# 2026-01-18_TinZr_Rev5_EasyEDA_project.net
KiCad netlist of a schematic drawn in EasyEDA Pro
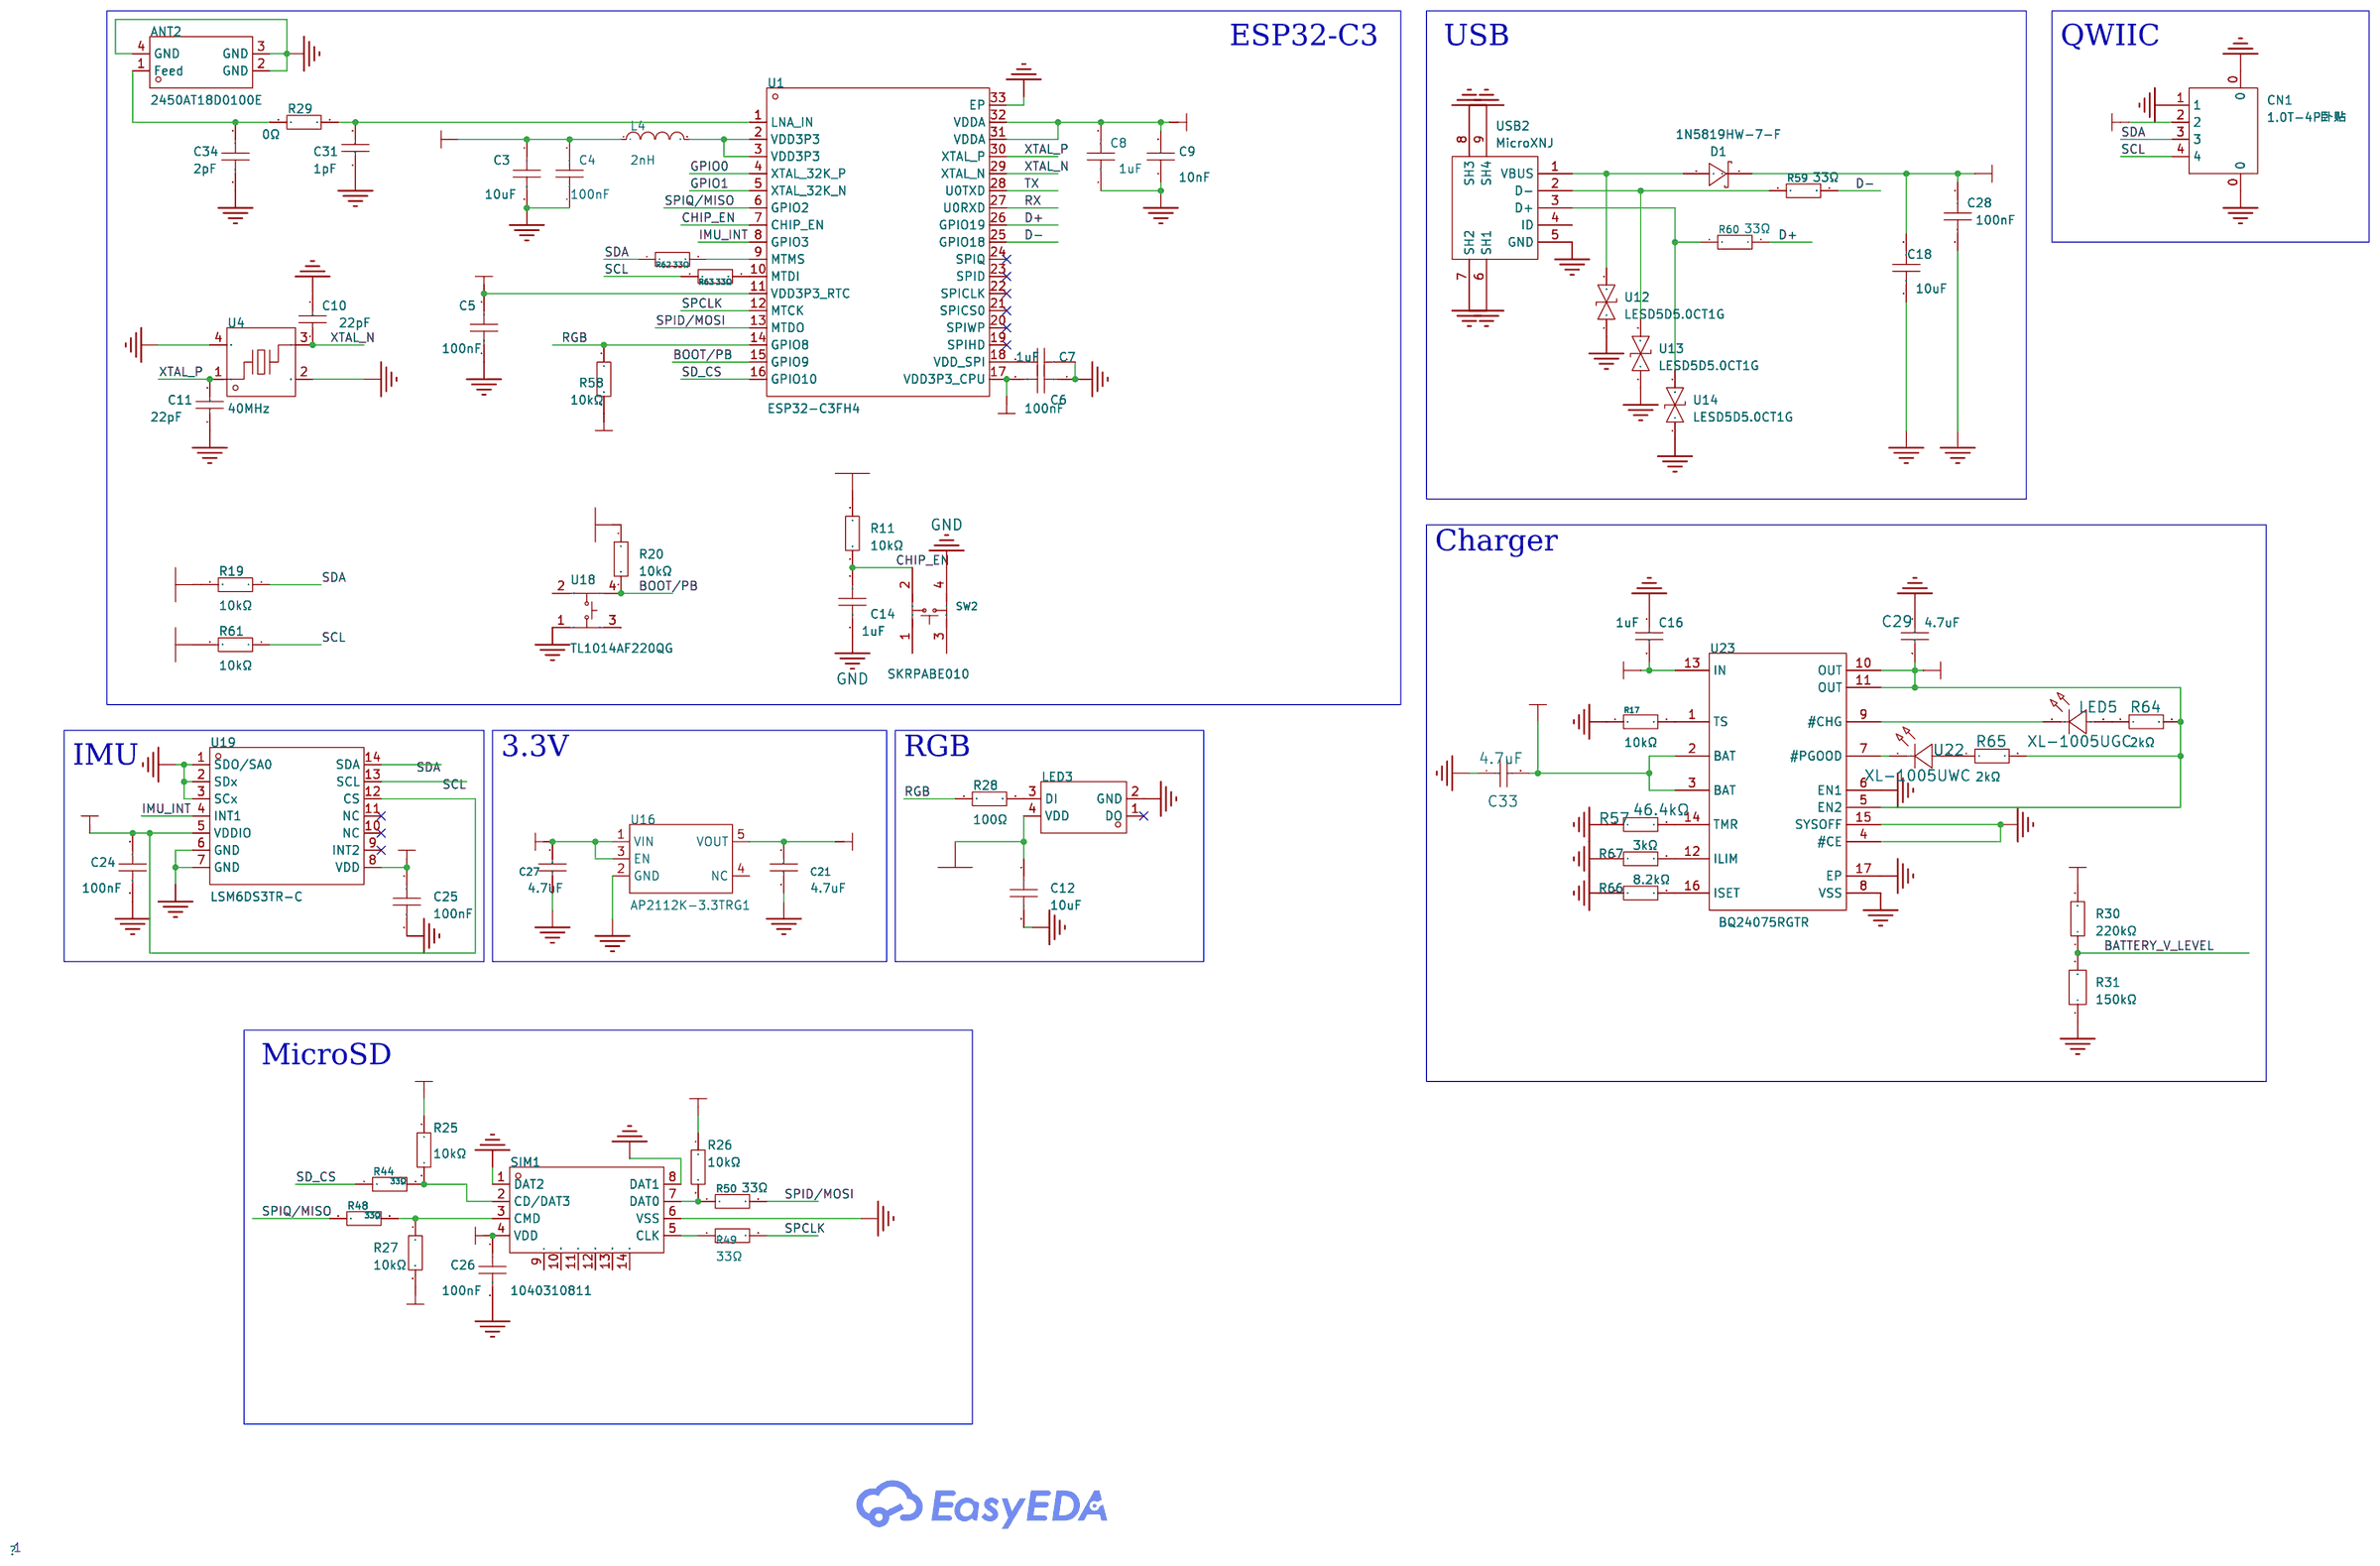
[diagram p0: schematic sheet]

(export (version "E")
  (design (tool "Eeschema 10.0.6"))
  (components
    (comp (ref "ANT2")
      (value "2450AT18D0100E")
      (footprint "easyedapro:ANT-SMD_4P-L3.2-W1.6")
      (fields (field (name "Manufacturer") "JOHANSON(约翰逊)"))
      (libsource (lib "easyedapro") (part "2450AT18D0100E"))
    )
    (comp (ref "C3")
      (value "10uF")
      (footprint "easyedapro:C0603")
      (description "容值:10uF;精度:±10%;额定电压:10V;材质(温度系数):X5R;")
      (fields
        (field (name "Manufacturer Part") "CL05A106MP5NUNC")
        (field (name "Manufacturer") "SAMSUNG(三星)")
      )
      (libsource (lib "easyedapro") (part "CL10A106KP8NNNC"))
    )
    (comp (ref "C4")
      (value "100nF")
      (footprint "easyedapro:C0402")
      (description "容值:100nF;精度:±10%;额定电压:16V;材质(温度系数):X7R;")
      (fields
        (field (name "Manufacturer Part") "CL05B104KO5NNNC")
        (field (name "Manufacturer") "SAMSUNG(三星)")
      )
      (libsource (lib "easyedapro") (part "CL05B104KO5NNNC"))
    )
    (comp (ref "C5")
      (value "100nF")
      (footprint "easyedapro:C0402")
      (description "容值:100nF;精度:±10%;额定电压:16V;材质(温度系数):X7R;")
      (fields
        (field (name "Manufacturer Part") "CL05B104KO5NNNC")
        (field (name "Manufacturer") "SAMSUNG(三星)")
      )
      (libsource (lib "easyedapro") (part "CL05B104KO5NNNC"))
    )
    (comp (ref "C6")
      (value "100nF")
      (footprint "easyedapro:C0402")
      (description "容值:100nF;精度:±10%;额定电压:16V;材质(温度系数):X7R;")
      (fields
        (field (name "Manufacturer Part") "CL05B104KO5NNNC")
        (field (name "Manufacturer") "SAMSUNG(三星)")
      )
      (libsource (lib "easyedapro") (part "CL05B104KO5NNNC"))
    )
    (comp (ref "C7")
      (value "1uF")
      (fields
        (field (name "Manufacturer Part") "CL05A105KA5NQNC")
        (field (name "Manufacturer") "SAMSUNG(三星)")
      )
      (libsource (lib "easyedapro") (part "CL05A105KA5NQNC"))
    )
    (comp (ref "C8")
      (value "1uF")
      (fields
        (field (name "Manufacturer Part") "CL05A105KA5NQNC")
        (field (name "Manufacturer") "SAMSUNG(三星)")
      )
      (libsource (lib "easyedapro") (part "CL05A105KA5NQNC"))
    )
    (comp (ref "C9")
      (value "10nF")
      (footprint "easyedapro:C0402")
      (description "容值:10nF;精度:±10%;额定电压:50V;材质(温度系数):X7R;")
      (fields
        (field (name "Manufacturer Part") "CL05B103KB5NNNC")
        (field (name "Manufacturer") "SAMSUNG(三星)")
      )
      (libsource (lib "easyedapro") (part "CL05B103KB5NNNC"))
    )
    (comp (ref "C10")
      (value "22pF")
      (footprint "easyedapro:C0402")
      (description "容值:22pF;精度:±5%;额定电压:50V;材质(温度系数):C0G;")
      (fields (field (name "Manufacturer Part") "0402CG220J500NT") (field (name "Manufacturer") "FH(风华)"))
      (libsource (lib "easyedapro") (part "0402CG220J500NT"))
    )
    (comp (ref "C11")
      (value "22pF")
      (footprint "easyedapro:C0402")
      (description "容值:22pF;精度:±5%;额定电压:50V;材质(温度系数):C0G;")
      (fields (field (name "Manufacturer Part") "0402CG220J500NT") (field (name "Manufacturer") "FH(风华)"))
      (libsource (lib "easyedapro") (part "0402CG220J500NT"))
    )
    (comp (ref "C12")
      (value "10uF")
      (footprint "easyedapro:C0603")
      (description "容值:10uF;精度:±10%;额定电压:10V;材质(温度系数):X5R;")
      (fields
        (field (name "Manufacturer Part") "CL05A106MP5NUNC")
        (field (name "Manufacturer") "SAMSUNG(三星)")
      )
      (libsource (lib "easyedapro") (part "CL10A106KP8NNNC"))
    )
    (comp (ref "C14")
      (value "1uF")
      (fields
        (field (name "Manufacturer Part") "CL05A105KA5NQNC")
        (field (name "Manufacturer") "SAMSUNG(三星)")
      )
      (libsource (lib "easyedapro") (part "CL05A105KA5NQNC"))
    )
    (comp (ref "C16")
      (value "1uF")
      (footprint "easyedapro:C0402")
      (fields
        (field (name "Manufacturer Part") "LMK105BJ105KV-F")
        (field (name "Manufacturer") "TAIYO YUDEN(太诱)")
      )
      (libsource (lib "easyedapro") (part "LMK105BJ105KV-F"))
    )
    (comp (ref "C18")
      (value "10uF")
      (footprint "easyedapro:C0805")
      (fields
        (field (name "Manufacturer Part") "CL21A106KAYNNNE")
        (field (name "Manufacturer") "SAMSUNG(三星)")
      )
      (libsource (lib "easyedapro") (part "CL21A106KAYNNNE"))
    )
    (comp (ref "C21")
      (value "4.7uF")
      (footprint "easyedapro:C0603")
      (fields
        (field (name "Manufacturer Part") "CL10A475KO8NNNC")
        (field (name "Manufacturer") "SAMSUNG(三星)")
      )
      (libsource (lib "easyedapro") (part "CL10A475KP8NNNC"))
    )
    (comp (ref "C24")
      (value "100nF")
      (footprint "easyedapro:C0402")
      (description "容值:100nF;精度:±10%;额定电压:16V;材质(温度系数):X7R;")
      (fields
        (field (name "Manufacturer Part") "CL05B104KO5NNNC")
        (field (name "Manufacturer") "SAMSUNG(三星)")
      )
      (libsource (lib "easyedapro") (part "CL05B104KO5NNNC"))
    )
    (comp (ref "C25")
      (value "100nF")
      (footprint "easyedapro:C0402")
      (description "容值:100nF;精度:±10%;额定电压:16V;材质(温度系数):X7R;")
      (fields
        (field (name "Manufacturer Part") "CL05B104KO5NNNC")
        (field (name "Manufacturer") "SAMSUNG(三星)")
      )
      (libsource (lib "easyedapro") (part "CL05B104KO5NNNC"))
    )
    (comp (ref "C26")
      (value "100nF")
      (footprint "easyedapro:C0402")
      (description "容值:100nF;精度:±10%;额定电压:16V;材质(温度系数):X7R;")
      (fields
        (field (name "Manufacturer Part") "CL05B104KO5NNNC")
        (field (name "Manufacturer") "SAMSUNG(三星)")
      )
      (libsource (lib "easyedapro") (part "CL05B104KO5NNNC"))
    )
    (comp (ref "C27")
      (value "4.7uF")
      (footprint "easyedapro:C0603")
      (fields
        (field (name "Manufacturer Part") "CL10A475KO8NNNC")
        (field (name "Manufacturer") "SAMSUNG(三星)")
      )
      (libsource (lib "easyedapro") (part "CL10A475KP8NNNC"))
    )
    (comp (ref "C28")
      (value "100nF")
      (footprint "easyedapro:C0402")
      (description "容值:100nF;精度:±10%;额定电压:16V;材质(温度系数):X7R;")
      (fields
        (field (name "Manufacturer Part") "CL05B104KO5NNNC")
        (field (name "Manufacturer") "SAMSUNG(三星)")
      )
      (libsource (lib "easyedapro") (part "CL05B104KO5NNNC"))
    )
    (comp (ref "C29")
      (value "4.7uF")
      (footprint "easyedapro:C0603")
      (fields
        (field (name "Manufacturer Part") "CL10A475KO8NNNC")
        (field (name "Manufacturer") "SAMSUNG(三星)")
      )
      (libsource (lib "easyedapro") (part "CL10A475KP8NNNC"))
    )
    (comp (ref "C31")
      (value "1pF")
      (footprint "easyedapro:C0402")
      (fields
        (field (name "Manufacturer Part") "GRM1555C1H1R0CA01D")
        (field (name "Manufacturer") "muRata(村田)")
      )
      (libsource (lib "easyedapro") (part "GRM1555C1H1R0CA01D"))
    )
    (comp (ref "C33")
      (value "4.7uF")
      (footprint "easyedapro:C0603")
      (fields
        (field (name "Manufacturer Part") "CL10A475KO8NNNC")
        (field (name "Manufacturer") "SAMSUNG(三星)")
      )
      (libsource (lib "easyedapro") (part "CL10A475KP8NNNC"))
    )
    (comp (ref "C34")
      (value "2pF")
      (footprint "easyedapro:C0402")
      (description "Capacitance:2pF Voltage Rating:50V Temperature Coefficient:NP0")
      (fields (field (name "Manufacturer Part") "CGA2B2NP01H020C050BA") (field (name "Manufacturer") "TDK"))
      (libsource (lib "easyedapro") (part "CGA2B2NP01H020C050BA"))
    )
    (comp (ref "CN1")
      (value "1.0T-4P卧贴")
      (footprint "easyedapro:CONN-SMD_1.0T-4P")
      (fields (field (name "Manufacturer") "BOOMELE(博穆精密)"))
      (libsource (lib "easyedapro") (part "1.0T-4P_C145956"))
    )
    (comp (ref "D1")
      (value "1N5819HW-7-F")
      (footprint "easyedapro:SOD-123_L2.7-W1.6-LS3.7-RD")
      (fields (field (name "Manufacturer") "DIODES(美台)"))
      (libsource (lib "easyedapro") (part "1N5819HW-7-F"))
    )
    (comp (ref "L4")
      (value "2nH")
      (footprint "easyedapro:L0603")
      (fields
        (field (name "Manufacturer Part") "SDCL1608C2N0STDF")
        (field (name "Manufacturer") "Sunlord(顺络)")
      )
      (libsource (lib "easyedapro") (part "SDCL1608C2N0STDF_C370234"))
    )
    (comp (ref "LED3")
      (value "WS2812C-2020-V1")
      (footprint "easyedapro:LED-SMD_4P-L2.0-W2.0-TL_WS2812B-2020")
      (description "小电流，小尺寸，适用于小尺寸，小间距产品，散热好，汽车氛围灯")
      (fields (field (name "Manufacturer") "worldsemi"))
      (libsource (lib "easyedapro") (part "WS2812C-2020-V1"))
    )
    (comp (ref "LED5")
      (value "XL-1005UGC")
      (footprint "easyedapro:LED0402-RD_GREEN")
      (fields (field (name "Manufacturer") "XINGLIGHT(成兴光)"))
      (libsource (lib "easyedapro") (part "XL-1005UGC"))
    )
    (comp (ref "R11")
      (value "10kΩ")
      (footprint "easyedapro:R0603")
      (description "电阻类型:厚膜电阻;阻值:10kΩ;精度:±1%;功率:1/10W;温度系数:±100ppm/;最大工作电压:75V;工作温度范围:-55~+155;")
      (fields
        (field (name "Manufacturer Part") "0603WAF1002T5E")
        (field (name "Manufacturer") "UNI-ROYAL(厚声)")
      )
      (libsource (lib "easyedapro") (part "0603WAF1002T5E"))
    )
    (comp (ref "R17")
      (value "10kΩ")
      (footprint "easyedapro:R0603")
      (fields
        (field (name "Manufacturer Part") "0603WAF1002T5E")
        (field (name "Manufacturer") "UNI-ROYAL(厚声)")
      )
      (libsource (lib "") (part "0603WAF1002T5E_1"))
    )
    (comp (ref "R19")
      (value "10kΩ")
      (footprint "easyedapro:R0603")
      (description "电阻类型:厚膜电阻;阻值:10kΩ;精度:±1%;功率:1/10W;温度系数:±100ppm/;最大工作电压:75V;工作温度范围:-55~+155;")
      (fields
        (field (name "Manufacturer Part") "0603WAF1002T5E")
        (field (name "Manufacturer") "UNI-ROYAL(厚声)")
      )
      (libsource (lib "easyedapro") (part "0603WAF1002T5E"))
    )
    (comp (ref "R20")
      (value "10kΩ")
      (footprint "easyedapro:R0603")
      (description "电阻类型:厚膜电阻;阻值:10kΩ;精度:±1%;功率:1/10W;温度系数:±100ppm/;最大工作电压:75V;工作温度范围:-55~+155;")
      (fields
        (field (name "Manufacturer Part") "0603WAF1002T5E")
        (field (name "Manufacturer") "UNI-ROYAL(厚声)")
      )
      (libsource (lib "easyedapro") (part "0603WAF1002T5E"))
    )
    (comp (ref "R25")
      (value "10kΩ")
      (footprint "easyedapro:R0603")
      (description "电阻类型:厚膜电阻;阻值:10kΩ;精度:±1%;功率:1/10W;温度系数:±100ppm/;最大工作电压:75V;工作温度范围:-55~+155;")
      (fields
        (field (name "Manufacturer Part") "0603WAF1002T5E")
        (field (name "Manufacturer") "UNI-ROYAL(厚声)")
      )
      (libsource (lib "easyedapro") (part "0603WAF1002T5E"))
    )
    (comp (ref "R26")
      (value "10kΩ")
      (footprint "easyedapro:R0603")
      (description "电阻类型:厚膜电阻;阻值:10kΩ;精度:±1%;功率:1/10W;温度系数:±100ppm/;最大工作电压:75V;工作温度范围:-55~+155;")
      (fields
        (field (name "Manufacturer Part") "0603WAF1002T5E")
        (field (name "Manufacturer") "UNI-ROYAL(厚声)")
      )
      (libsource (lib "easyedapro") (part "0603WAF1002T5E"))
    )
    (comp (ref "R27")
      (value "10kΩ")
      (footprint "easyedapro:R0603")
      (description "电阻类型:厚膜电阻;阻值:10kΩ;精度:±1%;功率:1/10W;温度系数:±100ppm/;最大工作电压:75V;工作温度范围:-55~+155;")
      (fields
        (field (name "Manufacturer Part") "0603WAF1002T5E")
        (field (name "Manufacturer") "UNI-ROYAL(厚声)")
      )
      (libsource (lib "easyedapro") (part "0603WAF1002T5E"))
    )
    (comp (ref "R28")
      (value "100Ω")
      (footprint "easyedapro:R0402")
      (fields (field (name "Manufacturer Part") "RC0402FR-07100RL") (field (name "Manufacturer") "YAGEO(国巨)"))
      (libsource (lib "easyedapro") (part "RC0402FR-07100RL"))
    )
    (comp (ref "R29")
      (value "0Ω")
      (footprint "easyedapro:R0402")
      (fields (field (name "Manufacturer Part") "RC0402JR-070RL") (field (name "Manufacturer") "YAGEO(国巨)"))
      (libsource (lib "easyedapro") (part "RC0402JR-070RL"))
    )
    (comp (ref "R30")
      (value "220kΩ")
      (footprint "easyedapro:R0402")
      (fields (field (name "Manufacturer Part") "RC0402JR-07220KL") (field (name "Manufacturer") "YAGEO(国巨)"))
      (libsource (lib "easyedapro") (part "RC0402JR-07220KL"))
    )
    (comp (ref "R31")
      (value "150kΩ")
      (footprint "easyedapro:R0402")
      (fields (field (name "Manufacturer Part") "FRC0402F1503TS") (field (name "Manufacturer") "FOJAN(富捷)"))
      (libsource (lib "easyedapro") (part "FRC0402F1503TS"))
    )
    (comp (ref "R44")
      (value "33Ω")
      (footprint "easyedapro:R0402")
      (fields
        (field (name "Manufacturer Part") "0402WGF330JTCE")
        (field (name "Manufacturer") "UNI-ROYAL(厚声)")
      )
      (libsource (lib "easyedapro") (part "0402WGF330JTCE"))
    )
    (comp (ref "R48")
      (value "33Ω")
      (footprint "easyedapro:R0402")
      (fields
        (field (name "Manufacturer Part") "0402WGF330JTCE")
        (field (name "Manufacturer") "UNI-ROYAL(厚声)")
      )
      (libsource (lib "easyedapro") (part "0402WGF330JTCE"))
    )
    (comp (ref "R49")
      (value "33Ω")
      (footprint "easyedapro:R0402")
      (fields
        (field (name "Manufacturer Part") "0402WGF330JTCE")
        (field (name "Manufacturer") "UNI-ROYAL(厚声)")
      )
      (libsource (lib "easyedapro") (part "0402WGF330JTCE"))
    )
    (comp (ref "R50")
      (value "33Ω")
      (footprint "easyedapro:R0402")
      (fields
        (field (name "Manufacturer Part") "0402WGF330JTCE")
        (field (name "Manufacturer") "UNI-ROYAL(厚声)")
      )
      (libsource (lib "easyedapro") (part "0402WGF330JTCE"))
    )
    (comp (ref "R57")
      (value "46.4kΩ")
      (footprint "easyedapro:R0402")
      (fields (field (name "Manufacturer Part") "RC0402FR-0746K4L") (field (name "Manufacturer") "YAGEO(国巨)"))
      (libsource (lib "easyedapro") (part "RC0402FR-0746K4L"))
    )
    (comp (ref "R58")
      (value "10kΩ")
      (footprint "easyedapro:R0603")
      (description "电阻类型:厚膜电阻;阻值:10kΩ;精度:±1%;功率:1/10W;温度系数:±100ppm/;最大工作电压:75V;工作温度范围:-55~+155;")
      (fields
        (field (name "Manufacturer Part") "0603WAF1002T5E")
        (field (name "Manufacturer") "UNI-ROYAL(厚声)")
      )
      (libsource (lib "easyedapro") (part "0603WAF1002T5E"))
    )
    (comp (ref "R59")
      (value "33Ω")
      (footprint "easyedapro:R0402")
      (fields
        (field (name "Manufacturer Part") "0402WGF330JTCE")
        (field (name "Manufacturer") "UNI-ROYAL(厚声)")
      )
      (libsource (lib "easyedapro") (part "0402WGF330JTCE"))
    )
    (comp (ref "R60")
      (value "33Ω")
      (footprint "easyedapro:R0402")
      (fields
        (field (name "Manufacturer Part") "0402WGF330JTCE")
        (field (name "Manufacturer") "UNI-ROYAL(厚声)")
      )
      (libsource (lib "easyedapro") (part "0402WGF330JTCE"))
    )
    (comp (ref "R61")
      (value "10kΩ")
      (footprint "easyedapro:R0603")
      (description "电阻类型:厚膜电阻;阻值:10kΩ;精度:±1%;功率:1/10W;温度系数:±100ppm/;最大工作电压:75V;工作温度范围:-55~+155;")
      (fields
        (field (name "Manufacturer Part") "0603WAF1002T5E")
        (field (name "Manufacturer") "UNI-ROYAL(厚声)")
      )
      (libsource (lib "easyedapro") (part "0603WAF1002T5E"))
    )
    (comp (ref "R62")
      (value "33Ω")
      (footprint "easyedapro:R0402")
      (fields
        (field (name "Manufacturer Part") "0402WGF330JTCE")
        (field (name "Manufacturer") "UNI-ROYAL(厚声)")
      )
      (libsource (lib "easyedapro") (part "0402WGF330JTCE"))
    )
    (comp (ref "R63")
      (value "33Ω")
      (footprint "easyedapro:R0402")
      (fields
        (field (name "Manufacturer Part") "0402WGF330JTCE")
        (field (name "Manufacturer") "UNI-ROYAL(厚声)")
      )
      (libsource (lib "easyedapro") (part "0402WGF330JTCE"))
    )
    (comp (ref "R64")
      (value "2kΩ")
      (footprint "easyedapro:R0402")
      (fields
        (field (name "Manufacturer Part") "0402WGF2001TCE")
        (field (name "Manufacturer") "UNI-ROYAL(厚声)")
      )
      (libsource (lib "easyedapro") (part "0402WGF2001TCE"))
    )
    (comp (ref "R65")
      (value "2kΩ")
      (footprint "easyedapro:R0402")
      (fields
        (field (name "Manufacturer Part") "0402WGF2001TCE")
        (field (name "Manufacturer") "UNI-ROYAL(厚声)")
      )
      (libsource (lib "easyedapro") (part "0402WGF2001TCE"))
    )
    (comp (ref "R66")
      (value "8.2kΩ")
      (footprint "easyedapro:R0402")
      (fields (field (name "Manufacturer Part") "RC0402FR-078K2L") (field (name "Manufacturer") "YAGEO(国巨)"))
      (libsource (lib "easyedapro") (part "RC0402FR-078K2L"))
    )
    (comp (ref "R67")
      (value "3kΩ")
      (footprint "easyedapro:R0402")
      (fields (field (name "Manufacturer Part") "RC0402FR-073KL") (field (name "Manufacturer") "YAGEO(国巨)"))
      (libsource (lib "easyedapro") (part "RC0402FR-073KL"))
    )
    (comp (ref "SIM1")
      (value "1040310811")
      (footprint "easyedapro:SIM-SMD_8P-1040310811")
      (fields (field (name "Manufacturer") "MOLEX"))
      (libsource (lib "easyedapro") (part "1040310811"))
    )
    (comp (ref "SW2")
      (value "SKRPABE010")
      (footprint "easyedapro:KEY-SMD_4P-L4.2-W3.2-P2.20-LS4.6")
      (fields (field (name "Manufacturer") "ALPSALPINE(阿尔卑斯阿尔派)"))
      (libsource (lib "easyedapro") (part "SKRPABE010"))
    )
    (comp (ref "U1")
      (value "ESP32-C3FH4")
      (footprint "easyedapro:QFN-32_L5.0-W5.0-P0.50-TL-EP3.7")
      (fields (field (name "Manufacturer") "ESPRESSIF(乐鑫)"))
      (libsource (lib "easyedapro") (part "ESP32-C3FH4"))
    )
    (comp (ref "U4")
      (value "40MHz")
      (footprint "easyedapro:CRYSTAL-SMD_4P-L2.5-W2.0-BL")
      (description "晶振类型:贴片晶振;频率:40MHz;常温频差:±10ppm;外接负载电容:10pF;频率稳定度(全温):±20ppm;")
      (fields (field (name "Manufacturer Part") "X252040MMB4SI") (field (name "Manufacturer") "YXC(扬兴晶振)"))
      (libsource (lib "easyedapro") (part "X252040MMB4SI"))
    )
    (comp (ref "U12")
      (value "LESD5D5.0CT1G")
      (footprint "easyedapro:SOD-523_L1.2-W0.8-LS1.6-BI")
      (fields (field (name "Manufacturer") "Leiditech(雷卯电子)"))
      (libsource (lib "easyedapro") (part "LESD5D5.0CT1G_C5246195"))
    )
    (comp (ref "U13")
      (value "LESD5D5.0CT1G")
      (footprint "easyedapro:SOD-523_L1.2-W0.8-LS1.6-BI")
      (fields (field (name "Manufacturer") "Leiditech(雷卯电子)"))
      (libsource (lib "easyedapro") (part "LESD5D5.0CT1G_C5246195"))
    )
    (comp (ref "U14")
      (value "LESD5D5.0CT1G")
      (footprint "easyedapro:SOD-523_L1.2-W0.8-LS1.6-BI")
      (fields (field (name "Manufacturer") "Leiditech(雷卯电子)"))
      (libsource (lib "easyedapro") (part "LESD5D5.0CT1G_C5246195"))
    )
    (comp (ref "U16")
      (value "AP2112K-3.3TRG1")
      (footprint "easyedapro:SOT-23-5_L2.9-W1.6-P0.95-LS2.8-BR")
      (fields (field (name "Manufacturer") "TECH PUBLIC(台舟)"))
      (libsource (lib "easyedapro") (part "AP2112K-3.3TRG1_C23380830"))
    )
    (comp (ref "U18")
      (value "TL1014AF220QG")
      (footprint "easyedapro:SW-SMD_E-SWITCH_TL1014AFXXX")
      (fields (field (name "Manufacturer") "E-Switch"))
      (libsource (lib "easyedapro") (part "TL1014AF220QG"))
    )
    (comp (ref "U19")
      (value "LSM6DS3TR-C")
      (footprint "easyedapro:LGA-14_L3.0-W2.5-P0.50-TL")
      (fields (field (name "Manufacturer") "ST(意法半导体)"))
      (libsource (lib "easyedapro") (part "LSM6DS3TR-C"))
    )
    (comp (ref "U22")
      (value "XL-1005UWC")
      (footprint "easyedapro:LED0402-RD_YELLOW")
      (fields (field (name "Manufacturer") "XINGLIGHT(成兴光)"))
      (libsource (lib "easyedapro") (part "XL-1005UWC_C20613596"))
    )
    (comp (ref "U23")
      (value "BQ24075RGTR")
      (footprint "easyedapro:QFN-16_L3.0-W3.0-P0.50-TL-EP1.7")
      (fields (field (name "Manufacturer") "TI(德州仪器)"))
      (libsource (lib "easyedapro") (part "BQ24075RGTR"))
    )
    (comp (ref "USB2")
      (value "MicroXNJ")
      (footprint "easyedapro:MICRO-USB-SMD_MICROXNJ_1")
      (fields (field (name "Manufacturer") "SHOU HAN(首韩)"))
      (libsource (lib "easyedapro") (part "MICROXNJ"))
    )
  )
  (nets
    (net (code "1") (name "+3V3") (class "Default")
      (node (ref "C12") (pin "1") (pinfunction "1_1") (pintype "unspecified"))
      (node (ref "C21") (pin "2") (pinfunction "2_2") (pintype "input"))
      (node (ref "C24") (pin "1") (pinfunction "1_1") (pintype "unspecified"))
      (node (ref "C25") (pin "1") (pinfunction "1_1") (pintype "unspecified"))
      (node (ref "C26") (pin "1") (pinfunction "1_1") (pintype "unspecified"))
      (node (ref "C3") (pin "1") (pinfunction "1_1") (pintype "unspecified"))
      (node (ref "C4") (pin "2") (pinfunction "2_2") (pintype "unspecified"))
      (node (ref "C5") (pin "2") (pinfunction "2_2") (pintype "unspecified"))
      (node (ref "C6") (pin "2") (pinfunction "2_2") (pintype "unspecified"))
      (node (ref "C8") (pin "2") (pinfunction "2_2") (pintype "unspecified"))
      (node (ref "C9") (pin "2") (pinfunction "2_2") (pintype "input"))
      (node (ref "CN1") (pin "2") (pinfunction "2_2") (pintype "unspecified"))
      (node (ref "L4") (pin "1") (pinfunction "1_1") (pintype "unspecified"))
      (node (ref "LED3") (pin "4") (pinfunction "VDD_4") (pintype "unspecified"))
      (node (ref "R11") (pin "2") (pinfunction "2_2") (pintype "input"))
      (node (ref "R19") (pin "2") (pinfunction "2_2") (pintype "input"))
      (node (ref "R20") (pin "1") (pinfunction "1_1") (pintype "input"))
      (node (ref "R25") (pin "1") (pinfunction "1_1") (pintype "input"))
      (node (ref "R26") (pin "1") (pinfunction "1_1") (pintype "input"))
      (node (ref "R27") (pin "2") (pinfunction "2_2") (pintype "input"))
      (node (ref "R58") (pin "2") (pinfunction "2_2") (pintype "input"))
      (node (ref "R61") (pin "2") (pinfunction "2_2") (pintype "input"))
      (node (ref "SIM1") (pin "4") (pinfunction "VDD_4") (pintype "unspecified"))
      (node (ref "U1") (pin "11") (pinfunction "VDD3P3_RTC_11") (pintype "unspecified"))
      (node (ref "U1") (pin "17") (pinfunction "VDD3P3_CPU_17") (pintype "unspecified"))
      (node (ref "U1") (pin "31") (pinfunction "VDDA_31") (pintype "unspecified"))
      (node (ref "U1") (pin "32") (pinfunction "VDDA_32") (pintype "unspecified"))
      (node (ref "U16") (pin "5") (pinfunction "VOUT_5") (pintype "unspecified"))
      (node (ref "U19") (pin "12") (pinfunction "CS_12") (pintype "unspecified"))
      (node (ref "U19") (pin "5") (pinfunction "VDDIO_5") (pintype "unspecified"))
      (node (ref "U19") (pin "8") (pinfunction "VDD_8") (pintype "unspecified"))
    )
    (net (code "2") (name "/BATTERY_V_LEVEL") (class "Default")
      (node (ref "R30") (pin "1") (pinfunction "1_1") (pintype "input"))
      (node (ref "R31") (pin "2") (pinfunction "2_2") (pintype "unspecified"))
    )
    (net (code "3") (name "/BOOT{slash}PB") (class "Default")
      (node (ref "R20") (pin "2") (pinfunction "2_2") (pintype "input"))
      (node (ref "U1") (pin "15") (pinfunction "GPIO9_15") (pintype "unspecified"))
      (node (ref "U18") (pin "4") (pinfunction "4_4") (pintype "unspecified"))
    )
    (net (code "4") (name "/CHIP_EN") (class "Default")
      (node (ref "C14") (pin "2") (pinfunction "2_2") (pintype "unspecified"))
      (node (ref "R11") (pin "1") (pinfunction "1_1") (pintype "input"))
      (node (ref "SW2") (pin "2") (pinfunction "2_2") (pintype "input"))
      (node (ref "U1") (pin "7") (pinfunction "CHIP_EN_7") (pintype "unspecified"))
    )
    (net (code "5") (name "/D+") (class "Default")
      (node (ref "R60") (pin "2") (pinfunction "2_2") (pintype "input"))
      (node (ref "U1") (pin "26") (pinfunction "GPIO19_26") (pintype "unspecified"))
    )
    (net (code "6") (name "/D-") (class "Default")
      (node (ref "R59") (pin "2") (pinfunction "2_2") (pintype "input"))
      (node (ref "U1") (pin "25") (pinfunction "GPIO18_25") (pintype "unspecified"))
    )
    (net (code "7") (name "/GPIO0") (class "Default")
      (node (ref "U1") (pin "4") (pinfunction "XTAL_32K_P_4") (pintype "unspecified"))
    )
    (net (code "8") (name "/GPIO1") (class "Default")
      (node (ref "U1") (pin "5") (pinfunction "XTAL_32K_N_5") (pintype "unspecified"))
    )
    (net (code "9") (name "/IMU_INT") (class "Default")
      (node (ref "U1") (pin "8") (pinfunction "GPIO3_8") (pintype "unspecified"))
      (node (ref "U19") (pin "4") (pinfunction "INT1_4") (pintype "unspecified"))
    )
    (net (code "10") (name "/RGB") (class "Default")
      (node (ref "R28") (pin "1") (pinfunction "1_1") (pintype "input"))
      (node (ref "R58") (pin "1") (pinfunction "1_1") (pintype "input"))
      (node (ref "U1") (pin "14") (pinfunction "GPIO8_14") (pintype "unspecified"))
    )
    (net (code "11") (name "/RX") (class "Default")
      (node (ref "U1") (pin "27") (pinfunction "U0RXD_27") (pintype "unspecified"))
    )
    (net (code "12") (name "/SCL") (class "Default")
      (node (ref "CN1") (pin "4") (pinfunction "4_4") (pintype "unspecified"))
      (node (ref "R61") (pin "1") (pinfunction "1_1") (pintype "input"))
      (node (ref "R63") (pin "1") (pinfunction "1_1") (pintype "input"))
      (node (ref "U19") (pin "13") (pinfunction "SCL_13") (pintype "unspecified"))
    )
    (net (code "13") (name "/SDA") (class "Default")
      (node (ref "CN1") (pin "3") (pinfunction "3_3") (pintype "unspecified"))
      (node (ref "R19") (pin "1") (pinfunction "1_1") (pintype "input"))
      (node (ref "R62") (pin "1") (pinfunction "1_1") (pintype "input"))
      (node (ref "U19") (pin "14") (pinfunction "SDA_14") (pintype "unspecified"))
    )
    (net (code "14") (name "/SD_CS") (class "Default")
      (node (ref "R44") (pin "1") (pinfunction "1_1") (pintype "input"))
      (node (ref "U1") (pin "16") (pinfunction "GPIO10_16") (pintype "unspecified"))
    )
    (net (code "15") (name "/SPCLK") (class "Default")
      (node (ref "R49") (pin "2") (pinfunction "2_2") (pintype "input"))
      (node (ref "U1") (pin "12") (pinfunction "MTCK_12") (pintype "unspecified"))
    )
    (net (code "16") (name "/SPID{slash}MOSI") (class "Default")
      (node (ref "R50") (pin "2") (pinfunction "2_2") (pintype "input"))
      (node (ref "U1") (pin "13") (pinfunction "MTDO_13") (pintype "unspecified"))
    )
    (net (code "17") (name "/SPIQ{slash}MISO") (class "Default")
      (node (ref "R48") (pin "1") (pinfunction "1_1") (pintype "input"))
      (node (ref "U1") (pin "6") (pinfunction "GPIO2_6") (pintype "unspecified"))
    )
    (net (code "18") (name "/TX") (class "Default")
      (node (ref "U1") (pin "28") (pinfunction "U0TXD_28") (pintype "unspecified"))
    )
    (net (code "19") (name "/XTAL_N") (class "Default")
      (node (ref "C10") (pin "1") (pinfunction "1_1") (pintype "input"))
      (node (ref "U1") (pin "29") (pinfunction "XTAL_N_29") (pintype "unspecified"))
      (node (ref "U4") (pin "3") (pinfunction "3_3") (pintype "input"))
    )
    (net (code "20") (name "/XTAL_P") (class "Default")
      (node (ref "C11") (pin "2") (pinfunction "2_2") (pintype "input"))
      (node (ref "U1") (pin "30") (pinfunction "XTAL_P_30") (pintype "unspecified"))
      (node (ref "U4") (pin "1") (pinfunction "1_1") (pintype "input"))
    )
    (net (code "21") (name "BAT+") (class "Default")
      (node (ref "C33") (pin "2") (pinfunction "2_2") (pintype "input"))
      (node (ref "R30") (pin "2") (pinfunction "2_2") (pintype "input"))
      (node (ref "U23") (pin "2") (pinfunction "BAT_2") (pintype "unspecified"))
      (node (ref "U23") (pin "3") (pinfunction "BAT_3") (pintype "unspecified"))
    )
    (net (code "22") (name "GND") (class "Default")
      (node (ref "ANT2") (pin "2") (pinfunction "GND_2") (pintype "unspecified"))
      (node (ref "ANT2") (pin "3") (pinfunction "GND_3") (pintype "unspecified"))
      (node (ref "ANT2") (pin "4") (pinfunction "GND_4") (pintype "unspecified"))
      (node (ref "C10") (pin "2") (pinfunction "2_2") (pintype "input"))
      (node (ref "C11") (pin "1") (pinfunction "1_1") (pintype "input"))
      (node (ref "C12") (pin "2") (pinfunction "2_2") (pintype "unspecified"))
      (node (ref "C14") (pin "1") (pinfunction "1_1") (pintype "unspecified"))
      (node (ref "C16") (pin "1") (pinfunction "1_1") (pintype "input"))
      (node (ref "C18") (pin "1") (pinfunction "1_1") (pintype "unspecified"))
      (node (ref "C21") (pin "1") (pinfunction "1_1") (pintype "input"))
      (node (ref "C24") (pin "2") (pinfunction "2_2") (pintype "unspecified"))
      (node (ref "C25") (pin "2") (pinfunction "2_2") (pintype "unspecified"))
      (node (ref "C26") (pin "2") (pinfunction "2_2") (pintype "unspecified"))
      (node (ref "C27") (pin "1") (pinfunction "1_1") (pintype "input"))
      (node (ref "C28") (pin "2") (pinfunction "2_2") (pintype "unspecified"))
      (node (ref "C29") (pin "1") (pinfunction "1_1") (pintype "input"))
      (node (ref "C3") (pin "2") (pinfunction "2_2") (pintype "unspecified"))
      (node (ref "C31") (pin "1") (pinfunction "1_1") (pintype "input"))
      (node (ref "C33") (pin "1") (pinfunction "1_1") (pintype "input"))
      (node (ref "C34") (pin "1") (pinfunction "1_1") (pintype "unspecified"))
      (node (ref "C4") (pin "1") (pinfunction "1_1") (pintype "unspecified"))
      (node (ref "C5") (pin "1") (pinfunction "1_1") (pintype "unspecified"))
      (node (ref "C6") (pin "1") (pinfunction "1_1") (pintype "unspecified"))
      (node (ref "C7") (pin "1") (pinfunction "1_1") (pintype "unspecified"))
      (node (ref "C8") (pin "1") (pinfunction "1_1") (pintype "unspecified"))
      (node (ref "C9") (pin "1") (pinfunction "1_1") (pintype "input"))
      (node (ref "CN1") (pin "0") (pinfunction "0_0") (pintype "unspecified"))
      (node (ref "CN1") (pin "1") (pinfunction "1_1") (pintype "unspecified"))
      (node (ref "LED3") (pin "2") (pinfunction "GND_2") (pintype "unspecified"))
      (node (ref "R17") (pin "1") (pinfunction "1_1") (pintype "input"))
      (node (ref "R31") (pin "1") (pinfunction "1_1") (pintype "unspecified"))
      (node (ref "R57") (pin "1") (pinfunction "1_1") (pintype "unspecified"))
      (node (ref "R66") (pin "1") (pinfunction "1_1") (pintype "input"))
      (node (ref "R67") (pin "1") (pinfunction "1_1") (pintype "input"))
      (node (ref "SIM1") (pin "1") (pinfunction "DAT2_1") (pintype "unspecified"))
      (node (ref "SIM1") (pin "6") (pinfunction "VSS_6") (pintype "unspecified"))
      (node (ref "SIM1") (pin "8") (pinfunction "DAT1_8") (pintype "unspecified"))
      (node (ref "SW2") (pin "4") (pinfunction "4_4") (pintype "input"))
      (node (ref "U1") (pin "33") (pinfunction "EP_33") (pintype "unspecified"))
      (node (ref "U12") (pin "1") (pinfunction "1_1") (pintype "unspecified"))
      (node (ref "U13") (pin "1") (pinfunction "1_1") (pintype "unspecified"))
      (node (ref "U14") (pin "1") (pinfunction "1_1") (pintype "unspecified"))
      (node (ref "U16") (pin "2") (pinfunction "GND_2") (pintype "unspecified"))
      (node (ref "U18") (pin "1") (pinfunction "1_1") (pintype "unspecified"))
      (node (ref "U19") (pin "1") (pinfunction "SDO/SA0_1") (pintype "unspecified"))
      (node (ref "U19") (pin "2") (pinfunction "SDx_2") (pintype "unspecified"))
      (node (ref "U19") (pin "3") (pinfunction "SCx_3") (pintype "unspecified"))
      (node (ref "U19") (pin "6") (pinfunction "GND_6") (pintype "unspecified"))
      (node (ref "U19") (pin "7") (pinfunction "GND_7") (pintype "unspecified"))
      (node (ref "U23") (pin "15") (pinfunction "SYSOFF_15") (pintype "unspecified"))
      (node (ref "U23") (pin "17") (pinfunction "EP_17") (pintype "unspecified"))
      (node (ref "U23") (pin "4") (pinfunction "#CE_4") (pintype "unspecified"))
      (node (ref "U23") (pin "6") (pinfunction "EN1_6") (pintype "unspecified"))
      (node (ref "U23") (pin "8") (pinfunction "VSS_8") (pintype "unspecified"))
      (node (ref "U4") (pin "2") (pinfunction "GND_2") (pintype "input"))
      (node (ref "U4") (pin "4") (pinfunction "GND_4") (pintype "input"))
      (node (ref "USB2") (pin "5") (pinfunction "GND_5") (pintype "unspecified"))
      (node (ref "USB2") (pin "6") (pinfunction "SH1_6") (pintype "unspecified"))
      (node (ref "USB2") (pin "7") (pinfunction "SH2_7") (pintype "unspecified"))
      (node (ref "USB2") (pin "8") (pinfunction "SH3_8") (pintype "unspecified"))
      (node (ref "USB2") (pin "9") (pinfunction "SH4_9") (pintype "unspecified"))
    )
    (net (code "23") (name "Net-(ANT2-Feed)") (class "Default")
      (node (ref "ANT2") (pin "1") (pinfunction "Feed_1") (pintype "unspecified"))
      (node (ref "C34") (pin "2") (pinfunction "2_2") (pintype "unspecified"))
      (node (ref "R29") (pin "1") (pinfunction "1_1") (pintype "input"))
    )
    (net (code "24") (name "Net-(D1-A)") (class "Default")
      (node (ref "D1") (pin "2") (pinfunction "A_2") (pintype "unspecified"))
      (node (ref "U12") (pin "2") (pinfunction "2_2") (pintype "unspecified"))
      (node (ref "USB2") (pin "1") (pinfunction "VBUS_1") (pintype "unspecified"))
    )
    (net (code "25") (name "Net-(L4-Pad2)") (class "Default")
      (node (ref "L4") (pin "2") (pinfunction "2_2") (pintype "unspecified"))
      (node (ref "U1") (pin "2") (pinfunction "VDD3P3_2") (pintype "unspecified"))
      (node (ref "U1") (pin "3") (pinfunction "VDD3P3_3") (pintype "unspecified"))
    )
    (net (code "26") (name "Net-(LED3-DI)") (class "Default")
      (node (ref "LED3") (pin "3") (pinfunction "DI_3") (pintype "unspecified"))
      (node (ref "R28") (pin "2") (pinfunction "2_2") (pintype "input"))
    )
    (net (code "27") (name "Net-(LED5-A)") (class "Default")
      (node (ref "LED5") (pin "2") (pinfunction "A_2") (pintype "unspecified"))
      (node (ref "R64") (pin "1") (pinfunction "1_1") (pintype "input"))
    )
    (net (code "28") (name "Net-(LED5-K)") (class "Default")
      (node (ref "LED5") (pin "1") (pinfunction "K_1") (pintype "unspecified"))
      (node (ref "U23") (pin "9") (pinfunction "#CHG_9") (pintype "unspecified"))
    )
    (net (code "29") (name "Net-(SIM1-CD{slash}DAT3)") (class "Default")
      (node (ref "R25") (pin "2") (pinfunction "2_2") (pintype "input"))
      (node (ref "R44") (pin "2") (pinfunction "2_2") (pintype "input"))
      (node (ref "SIM1") (pin "2") (pinfunction "CD/DAT3_2") (pintype "unspecified"))
    )
    (net (code "30") (name "Net-(SIM1-CLK)") (class "Default")
      (node (ref "R49") (pin "1") (pinfunction "1_1") (pintype "input"))
      (node (ref "SIM1") (pin "5") (pinfunction "CLK_5") (pintype "unspecified"))
    )
    (net (code "31") (name "Net-(SIM1-CMD)") (class "Default")
      (node (ref "R27") (pin "1") (pinfunction "1_1") (pintype "input"))
      (node (ref "R48") (pin "2") (pinfunction "2_2") (pintype "input"))
      (node (ref "SIM1") (pin "3") (pinfunction "CMD_3") (pintype "unspecified"))
    )
    (net (code "32") (name "Net-(SIM1-DAT0)") (class "Default")
      (node (ref "R26") (pin "2") (pinfunction "2_2") (pintype "input"))
      (node (ref "R50") (pin "1") (pinfunction "1_1") (pintype "input"))
      (node (ref "SIM1") (pin "7") (pinfunction "DAT0_7") (pintype "unspecified"))
    )
    (net (code "33") (name "Net-(U1-LNA_IN)") (class "Default")
      (node (ref "C31") (pin "2") (pinfunction "2_2") (pintype "input"))
      (node (ref "R29") (pin "2") (pinfunction "2_2") (pintype "input"))
      (node (ref "U1") (pin "1") (pinfunction "LNA_IN_1") (pintype "unspecified"))
    )
    (net (code "34") (name "Net-(U1-MTDI)") (class "Default")
      (node (ref "R63") (pin "2") (pinfunction "2_2") (pintype "input"))
      (node (ref "U1") (pin "10") (pinfunction "MTDI_10") (pintype "unspecified"))
    )
    (net (code "35") (name "Net-(U1-MTMS)") (class "Default")
      (node (ref "R62") (pin "2") (pinfunction "2_2") (pintype "input"))
      (node (ref "U1") (pin "9") (pinfunction "MTMS_9") (pintype "unspecified"))
    )
    (net (code "36") (name "Net-(U1-VDD_SPI)") (class "Default")
      (node (ref "C7") (pin "2") (pinfunction "2_2") (pintype "unspecified"))
      (node (ref "U1") (pin "18") (pinfunction "VDD_SPI_18") (pintype "unspecified"))
    )
    (net (code "37") (name "Net-(U22-A)") (class "Default")
      (node (ref "R65") (pin "1") (pinfunction "1_1") (pintype "input"))
      (node (ref "U22") (pin "2") (pinfunction "A_2") (pintype "unspecified"))
    )
    (net (code "38") (name "Net-(U22-K)") (class "Default")
      (node (ref "U22") (pin "1") (pinfunction "K_1") (pintype "unspecified"))
      (node (ref "U23") (pin "7") (pinfunction "#PGOOD_7") (pintype "unspecified"))
    )
    (net (code "39") (name "Net-(U23-ILIM)") (class "Default")
      (node (ref "R67") (pin "2") (pinfunction "2_2") (pintype "input"))
      (node (ref "U23") (pin "12") (pinfunction "ILIM_12") (pintype "unspecified"))
    )
    (net (code "40") (name "Net-(U23-ISET)") (class "Default")
      (node (ref "R66") (pin "2") (pinfunction "2_2") (pintype "input"))
      (node (ref "U23") (pin "16") (pinfunction "ISET_16") (pintype "bidirectional"))
    )
    (net (code "41") (name "Net-(U23-TMR)") (class "Default")
      (node (ref "R57") (pin "2") (pinfunction "2_2") (pintype "unspecified"))
      (node (ref "U23") (pin "14") (pinfunction "TMR_14") (pintype "unspecified"))
    )
    (net (code "42") (name "Net-(U23-TS)") (class "Default")
      (node (ref "R17") (pin "2") (pinfunction "2_2") (pintype "input"))
      (node (ref "U23") (pin "1") (pinfunction "TS_1") (pintype "unspecified"))
    )
    (net (code "43") (name "Net-(USB2-D+)") (class "Default")
      (node (ref "R60") (pin "1") (pinfunction "1_1") (pintype "input"))
      (node (ref "U14") (pin "2") (pinfunction "2_2") (pintype "unspecified"))
      (node (ref "USB2") (pin "3") (pinfunction "D+_3") (pintype "unspecified"))
    )
    (net (code "44") (name "Net-(USB2-D-)") (class "Default")
      (node (ref "R59") (pin "1") (pinfunction "1_1") (pintype "input"))
      (node (ref "U13") (pin "2") (pinfunction "2_2") (pintype "unspecified"))
      (node (ref "USB2") (pin "2") (pinfunction "D-_2") (pintype "unspecified"))
    )
    (net (code "45") (name "POW") (class "Default")
      (node (ref "C27") (pin "2") (pinfunction "2_2") (pintype "input"))
      (node (ref "C29") (pin "2") (pinfunction "2_2") (pintype "input"))
      (node (ref "R64") (pin "2") (pinfunction "2_2") (pintype "input"))
      (node (ref "R65") (pin "2") (pinfunction "2_2") (pintype "input"))
      (node (ref "U16") (pin "1") (pinfunction "VIN_1") (pintype "unspecified"))
      (node (ref "U16") (pin "3") (pinfunction "EN_3") (pintype "unspecified"))
      (node (ref "U23") (pin "10") (pinfunction "OUT_10") (pintype "unspecified"))
      (node (ref "U23") (pin "11") (pinfunction "OUT_11") (pintype "unspecified"))
      (node (ref "U23") (pin "5") (pinfunction "EN2_5") (pintype "unspecified"))
    )
    (net (code "46") (name "VBUS") (class "Default")
      (node (ref "C16") (pin "2") (pinfunction "2_2") (pintype "input"))
      (node (ref "C18") (pin "2") (pinfunction "2_2") (pintype "unspecified"))
      (node (ref "C28") (pin "1") (pinfunction "1_1") (pintype "unspecified"))
      (node (ref "D1") (pin "1") (pinfunction "K_1") (pintype "unspecified"))
      (node (ref "U23") (pin "13") (pinfunction "IN_13") (pintype "unspecified"))
    )
    (net (code "47") (name "unconnected-(LED3-DO-Pad1)") (class "Default")
      (node (ref "LED3") (pin "1") (pinfunction "DO_1") (pintype "unspecified+no_connect"))
    )
    (net (code "48") (name "unconnected-(SIM1-Pad9)") (class "Default")
      (node (ref "SIM1") (pin "9") (pinfunction "9_9") (pintype "unspecified"))
    )
    (net (code "49") (name "unconnected-(SIM1-Pad10)") (class "Default")
      (node (ref "SIM1") (pin "10") (pinfunction "10_10") (pintype "unspecified"))
    )
    (net (code "50") (name "unconnected-(SIM1-Pad11)") (class "Default")
      (node (ref "SIM1") (pin "11") (pinfunction "11_11") (pintype "unspecified"))
    )
    (net (code "51") (name "unconnected-(SIM1-Pad12)") (class "Default")
      (node (ref "SIM1") (pin "12") (pinfunction "12_12") (pintype "unspecified"))
    )
    (net (code "52") (name "unconnected-(SIM1-Pad13)") (class "Default")
      (node (ref "SIM1") (pin "13") (pinfunction "13_13") (pintype "unspecified"))
    )
    (net (code "53") (name "unconnected-(SIM1-Pad14)") (class "Default")
      (node (ref "SIM1") (pin "14") (pinfunction "14_14") (pintype "unspecified"))
    )
    (net (code "54") (name "unconnected-(SW2-Pad1)") (class "Default")
      (node (ref "SW2") (pin "1") (pinfunction "1_1") (pintype "input"))
    )
    (net (code "55") (name "unconnected-(SW2-Pad3)") (class "Default")
      (node (ref "SW2") (pin "3") (pinfunction "3_3") (pintype "input"))
    )
    (net (code "56") (name "unconnected-(U1-SPICLK-Pad22)") (class "Default")
      (node (ref "U1") (pin "22") (pinfunction "SPICLK_22") (pintype "unspecified+no_connect"))
    )
    (net (code "57") (name "unconnected-(U1-SPICS0-Pad21)") (class "Default")
      (node (ref "U1") (pin "21") (pinfunction "SPICS0_21") (pintype "unspecified+no_connect"))
    )
    (net (code "58") (name "unconnected-(U1-SPID-Pad23)") (class "Default")
      (node (ref "U1") (pin "23") (pinfunction "SPID_23") (pintype "unspecified+no_connect"))
    )
    (net (code "59") (name "unconnected-(U1-SPIHD-Pad19)") (class "Default")
      (node (ref "U1") (pin "19") (pinfunction "SPIHD_19") (pintype "unspecified+no_connect"))
    )
    (net (code "60") (name "unconnected-(U1-SPIQ-Pad24)") (class "Default")
      (node (ref "U1") (pin "24") (pinfunction "SPIQ_24") (pintype "unspecified+no_connect"))
    )
    (net (code "61") (name "unconnected-(U1-SPIWP-Pad20)") (class "Default")
      (node (ref "U1") (pin "20") (pinfunction "SPIWP_20") (pintype "unspecified+no_connect"))
    )
    (net (code "62") (name "unconnected-(U16-NC-Pad4)") (class "Default")
      (node (ref "U16") (pin "4") (pinfunction "NC_4") (pintype "unspecified"))
    )
    (net (code "63") (name "unconnected-(U18-Pad2)") (class "Default")
      (node (ref "U18") (pin "2") (pinfunction "2_2") (pintype "unspecified"))
    )
    (net (code "64") (name "unconnected-(U18-Pad3)") (class "Default")
      (node (ref "U18") (pin "3") (pinfunction "3_3") (pintype "unspecified"))
    )
    (net (code "65") (name "unconnected-(U19-INT2-Pad9)") (class "Default")
      (node (ref "U19") (pin "9") (pinfunction "INT2_9") (pintype "unspecified+no_connect"))
    )
    (net (code "66") (name "unconnected-(U19-NC-Pad10)") (class "Default")
      (node (ref "U19") (pin "10") (pinfunction "NC_10") (pintype "unspecified+no_connect"))
    )
    (net (code "67") (name "unconnected-(U19-NC-Pad11)") (class "Default")
      (node (ref "U19") (pin "11") (pinfunction "NC_11") (pintype "unspecified+no_connect"))
    )
    (net (code "68") (name "unconnected-(USB2-ID-Pad4)") (class "Default")
      (node (ref "USB2") (pin "4") (pinfunction "ID_4") (pintype "unspecified"))
    )
  )
)
